# control.net
KiCad netlist of a schematic drawn in EAGLE
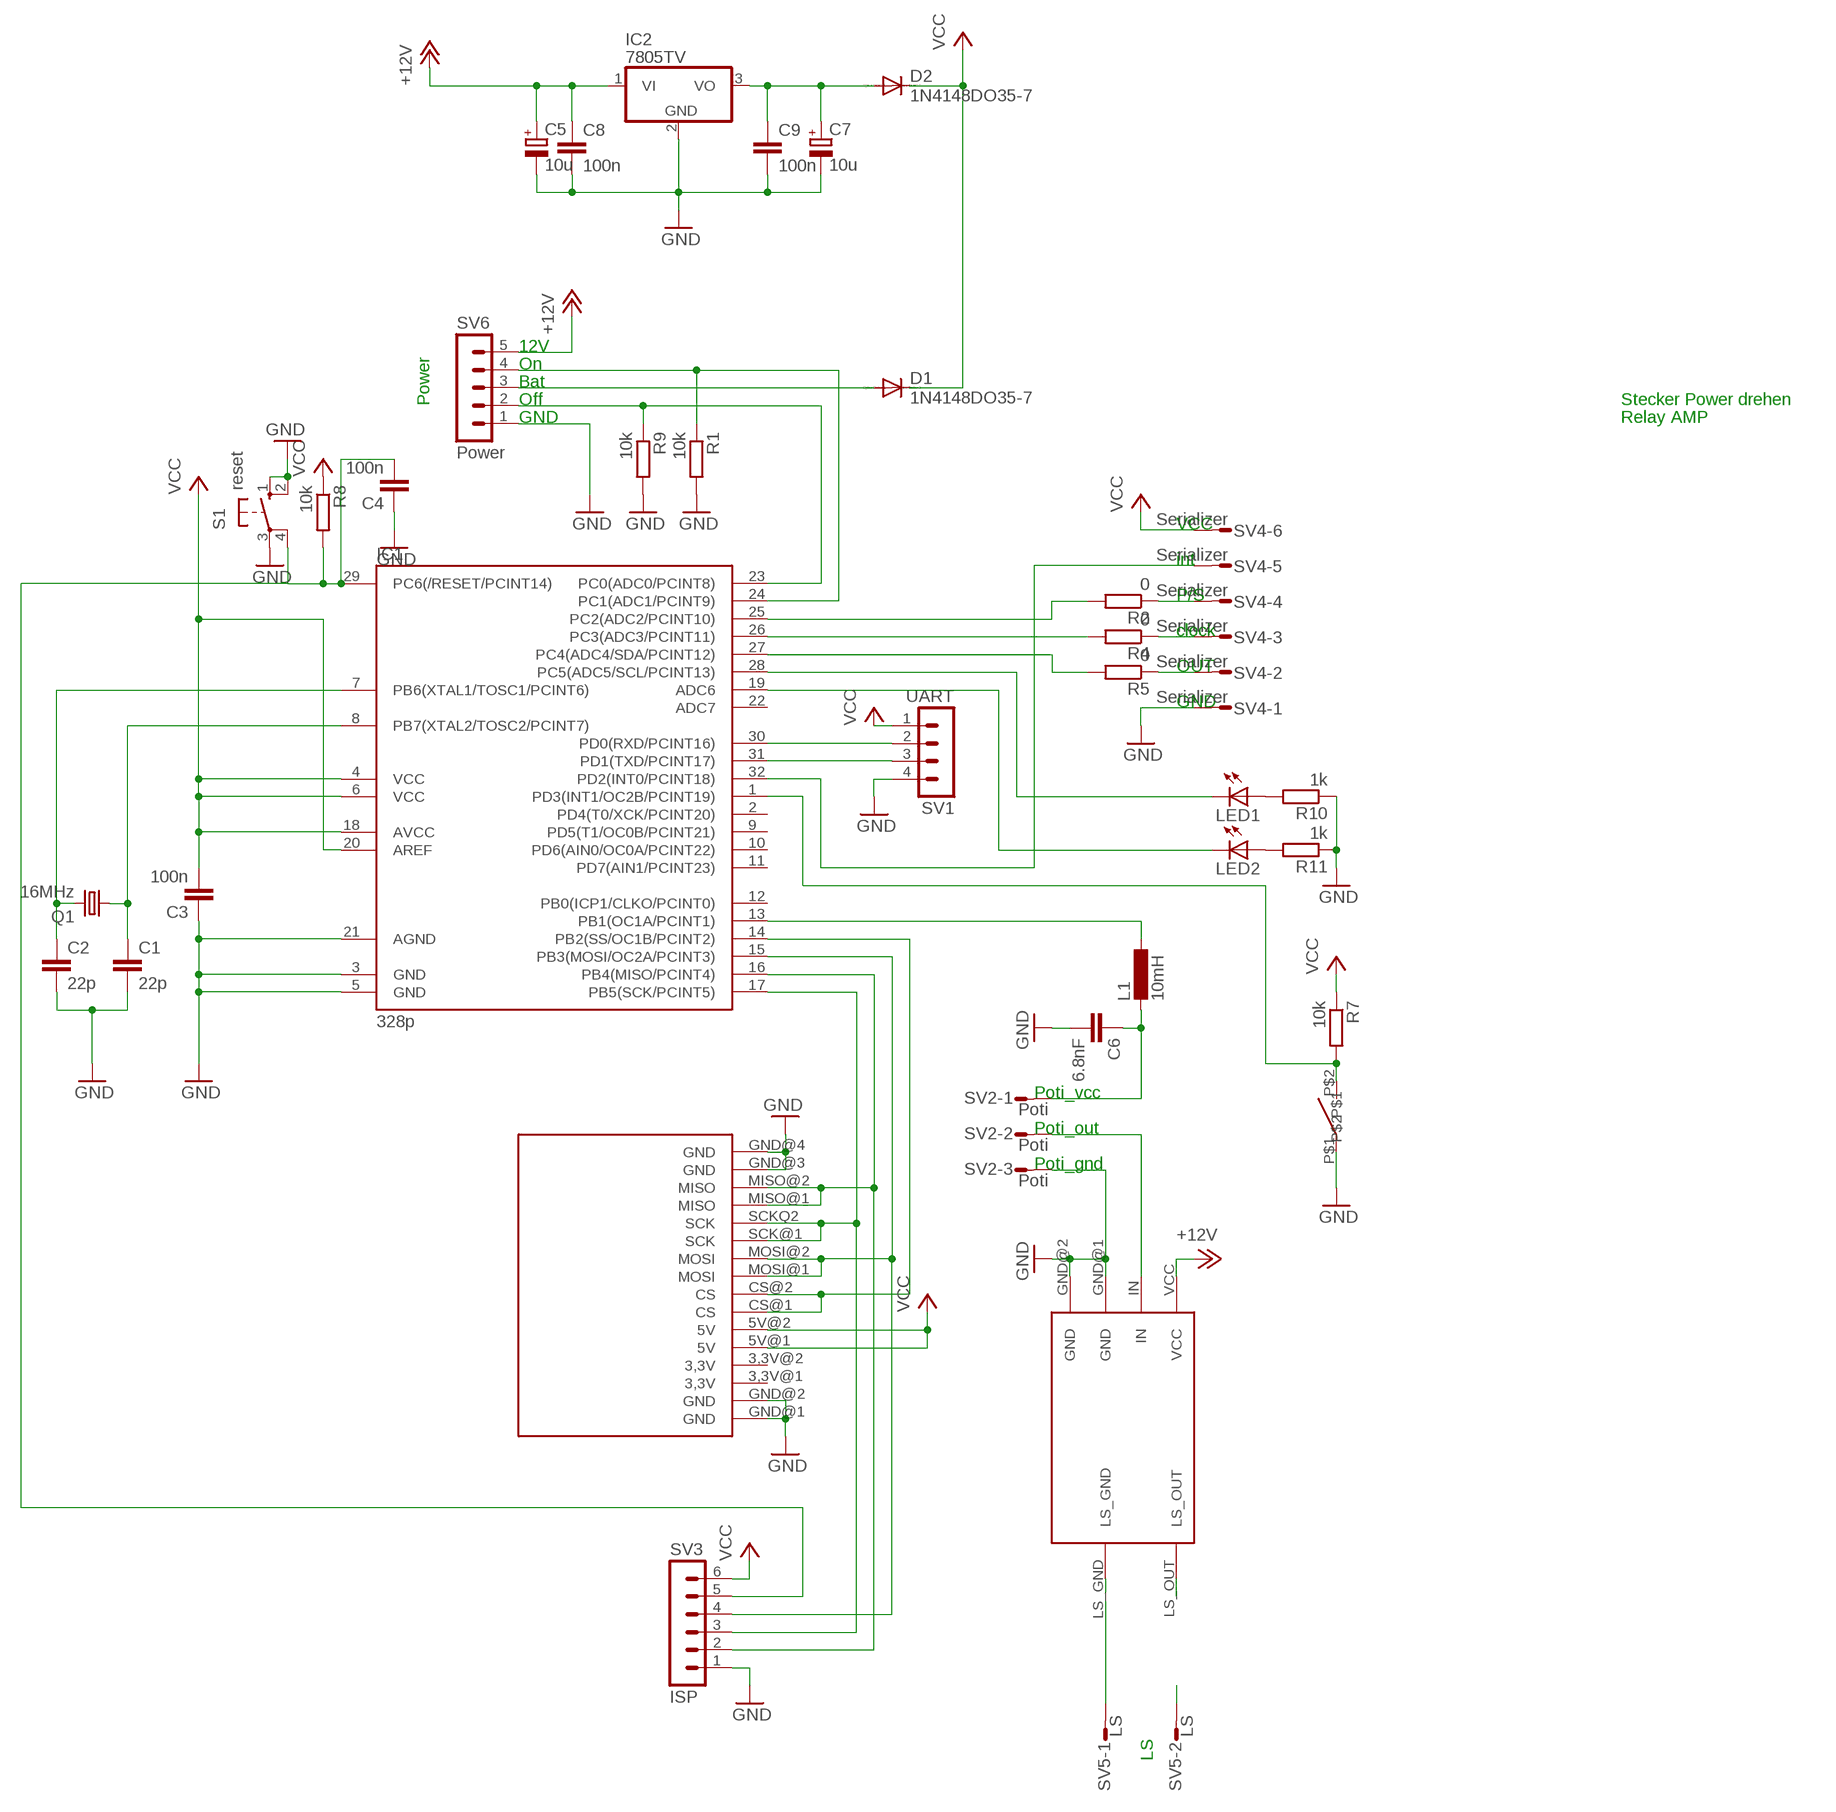
[diagram p0: schematic, sheet 1]

(export (version "E")
  (design (tool "Eeschema 10.0.6"))
  (components
    (comp (ref "C1")
      (value "22p")
      (footprint "eagle-import:C1206")
      (libsource (lib "eagle-import") (part "C-EUC1206"))
    )
    (comp (ref "C2")
      (value "22p")
      (footprint "eagle-import:C1206")
      (libsource (lib "eagle-import") (part "C-EUC1206"))
    )
    (comp (ref "C3")
      (value "100n")
      (footprint "eagle-import:C1206")
      (libsource (lib "eagle-import") (part "C-EUC1206"))
    )
    (comp (ref "C4")
      (value "100n")
      (footprint "eagle-import:C1206")
      (libsource (lib "eagle-import") (part "C-EUC1206"))
    )
    (comp (ref "C5")
      (value "10u")
      (footprint "eagle-import:E2,5-7")
      (libsource (lib "eagle-import") (part "CPOL-EUE2.5-7"))
    )
    (comp (ref "C6")
      (value "6.8nF")
      (footprint "eagle-import:C050-024X044")
      (libsource (lib "eagle-import") (part "C-EU050-024X044"))
    )
    (comp (ref "C7")
      (value "10u")
      (footprint "eagle-import:E2,5-7")
      (libsource (lib "eagle-import") (part "CPOL-EUE2.5-7"))
    )
    (comp (ref "C8")
      (value "100n")
      (footprint "eagle-import:C1206")
      (libsource (lib "eagle-import") (part "C-EUC1206"))
    )
    (comp (ref "C9")
      (value "100n")
      (footprint "eagle-import:C1206")
      (libsource (lib "eagle-import") (part "C-EUC1206"))
    )
    (comp (ref "D1")
      (value "1N4148DO35-7")
      (footprint "eagle-import:DO35-7")
      (libsource (lib "eagle-import") (part "1N4148DO35-7"))
    )
    (comp (ref "D2")
      (value "1N4148DO35-7")
      (footprint "eagle-import:DO35-7")
      (libsource (lib "eagle-import") (part "1N4148DO35-7"))
    )
    (comp (ref "IC1")
      (value "328p")
      (footprint "eagle-import:TQFP32-08")
      (libsource (lib "eagle-import") (part "MEGA48/88/168-AU"))
    )
    (comp (ref "IC2")
      (value "7805TV")
      (footprint "eagle-import:TO220V")
      (libsource (lib "eagle-import") (part "78TV05"))
    )
    (comp (ref "L1")
      (value "10mH")
      (footprint "eagle-import:0207_5V")
      (libsource (lib "eagle-import") (part "L-EU0207/5V"))
    )
    (comp (ref "LED1")
      (value "LEDCHIPLED_1206")
      (footprint "eagle-import:CHIPLED_1206")
      (libsource (lib "eagle-import") (part "LEDCHIPLED_1206"))
    )
    (comp (ref "LED2")
      (value "LEDCHIPLED_1206")
      (footprint "eagle-import:CHIPLED_1206")
      (libsource (lib "eagle-import") (part "LEDCHIPLED_1206"))
    )
    (comp (ref "Q1")
      (value "16MHz")
      (footprint "eagle-import:HC49UP")
      (libsource (lib "eagle-import") (part "CRYSTALHC49UP"))
    )
    (comp (ref "R1")
      (value "10k")
      (footprint "eagle-import:M1206")
      (libsource (lib "eagle-import") (part "R-EU_M1206"))
    )
    (comp (ref "R2")
      (value "0")
      (footprint "eagle-import:M1206")
      (libsource (lib "eagle-import") (part "R-EU_M1206"))
    )
    (comp (ref "R4")
      (value "0")
      (footprint "eagle-import:M1206")
      (libsource (lib "eagle-import") (part "R-EU_M1206"))
    )
    (comp (ref "R5")
      (value "0")
      (footprint "eagle-import:M1206")
      (libsource (lib "eagle-import") (part "R-EU_M1206"))
    )
    (comp (ref "R7")
      (value "10k")
      (footprint "eagle-import:M1206")
      (libsource (lib "eagle-import") (part "R-EU_M1206"))
    )
    (comp (ref "R8")
      (value "10k")
      (footprint "eagle-import:M1206")
      (libsource (lib "eagle-import") (part "R-EU_M1206"))
    )
    (comp (ref "R9")
      (value "10k")
      (footprint "eagle-import:M1206")
      (libsource (lib "eagle-import") (part "R-EU_M1206"))
    )
    (comp (ref "R10")
      (value "1k")
      (footprint "eagle-import:M1206")
      (libsource (lib "eagle-import") (part "R-EU_M1206"))
    )
    (comp (ref "R11")
      (value "1k")
      (footprint "eagle-import:M1206")
      (libsource (lib "eagle-import") (part "R-EU_M1206"))
    )
    (comp (ref "S1")
      (value "reset")
      (footprint "eagle-import:B3F-10XX")
      (fields (field (name "MPN") "B3F-1000"))
      (libsource (lib "eagle-import") (part "10-XX"))
    )
    (comp (ref "SV1")
      (value "UART")
      (footprint "eagle-import:MA04-1")
      (libsource (lib "eagle-import") (part "MA04-1"))
    )
    (comp (ref "SV2")
      (value "Poti")
      (footprint "eagle-import:S03P")
      (libsource (lib "eagle-import") (part "S03P"))
    )
    (comp (ref "SV3")
      (value "ISP")
      (footprint "eagle-import:MA06-1")
      (libsource (lib "eagle-import") (part "MA06-1"))
    )
    (comp (ref "SV4")
      (value "Serializer")
      (footprint "eagle-import:S06P")
      (libsource (lib "eagle-import") (part "S06P"))
    )
    (comp (ref "SV5")
      (value "LS")
      (footprint "eagle-import:S02P")
      (libsource (lib "eagle-import") (part "S02P"))
    )
    (comp (ref "SV6")
      (value "Power")
      (footprint "eagle-import:MA05-1")
      (libsource (lib "eagle-import") (part "MA05-1"))
    )
    (comp (ref "U$1")
      (value "TILT")
      (footprint "eagle-import:TILT")
      (libsource (lib "eagle-import") (part "TILT"))
    )
    (comp (ref "U$2")
      (value "AMP")
      (footprint "eagle-import:AMP")
      (libsource (lib "eagle-import") (part "AMP"))
    )
    (comp (ref "U$3")
      (value "SD_CARD_HOLDER")
      (footprint "eagle-import:SD_CARD_HOLDER")
      (libsource (lib "eagle-import") (part "SD_CARD_HOLDER"))
    )
  )
  (nets
    (net (code "1") (name "+12V") (class "Default")
      (node (ref "C5") (pin "+") (pinfunction "+_+") (pintype "passive"))
      (node (ref "C8") (pin "1") (pinfunction "1_1") (pintype "passive"))
      (node (ref "IC2") (pin "1") (pinfunction "VI_1") (pintype "input"))
      (node (ref "SV6") (pin "5") (pinfunction "5_5") (pintype "passive"))
      (node (ref "U$2") (pin "VCC") (pinfunction "VCC_VCC") (pintype "bidirectional"))
    )
    (net (code "2") (name "GND") (class "Default")
      (node (ref "C1") (pin "2") (pinfunction "2_2") (pintype "passive"))
      (node (ref "C2") (pin "2") (pinfunction "2_2") (pintype "passive"))
      (node (ref "C3") (pin "1") (pinfunction "1_1") (pintype "passive"))
      (node (ref "C4") (pin "1") (pinfunction "1_1") (pintype "passive"))
      (node (ref "C5") (pin "-") (pinfunction "-_-") (pintype "passive"))
      (node (ref "C6") (pin "2") (pinfunction "2_2") (pintype "passive"))
      (node (ref "C7") (pin "-") (pinfunction "-_-") (pintype "passive"))
      (node (ref "C8") (pin "2") (pinfunction "2_2") (pintype "passive"))
      (node (ref "C9") (pin "2") (pinfunction "2_2") (pintype "passive"))
      (node (ref "IC1") (pin "21") (pinfunction "AGND_21") (pintype "power_in"))
      (node (ref "IC1") (pin "3") (pinfunction "GND_3") (pintype "power_in"))
      (node (ref "IC1") (pin "5") (pinfunction "GND_5") (pintype "power_in"))
      (node (ref "IC2") (pin "2") (pinfunction "GND_2") (pintype "passive"))
      (node (ref "R1") (pin "2") (pinfunction "2_2") (pintype "passive"))
      (node (ref "R10") (pin "1") (pinfunction "1_1") (pintype "passive"))
      (node (ref "R11") (pin "1") (pinfunction "1_1") (pintype "passive"))
      (node (ref "R9") (pin "2") (pinfunction "2_2") (pintype "passive"))
      (node (ref "S1") (pin "1") (pinfunction "S_1") (pintype "passive"))
      (node (ref "S1") (pin "2") (pinfunction "S1_2") (pintype "passive"))
      (node (ref "S1") (pin "3") (pinfunction "P_3") (pintype "passive"))
      (node (ref "SV1") (pin "4") (pinfunction "4_4") (pintype "passive"))
      (node (ref "SV2") (pin "3") (pinfunction "S_3") (pintype "passive"))
      (node (ref "SV3") (pin "1") (pinfunction "1_1") (pintype "passive"))
      (node (ref "SV4") (pin "1") (pinfunction "S_1") (pintype "passive"))
      (node (ref "SV6") (pin "1") (pinfunction "1_1") (pintype "passive"))
      (node (ref "U$1") (pin "P$1") (pinfunction "P$1_P$1") (pintype "bidirectional"))
      (node (ref "U$2") (pin "GND@1") (pinfunction "GND_GND@1") (pintype "bidirectional"))
      (node (ref "U$2") (pin "GND@2") (pinfunction "GND_GND@2") (pintype "bidirectional"))
      (node (ref "U$3") (pin "GND@1") (pinfunction "GND_GND@1") (pintype "bidirectional"))
      (node (ref "U$3") (pin "GND@2") (pinfunction "GND_GND@2") (pintype "bidirectional"))
      (node (ref "U$3") (pin "GND@3") (pinfunction "GND_GND@3") (pintype "bidirectional"))
      (node (ref "U$3") (pin "GND@4") (pinfunction "GND_GND@4") (pintype "bidirectional"))
    )
    (net (code "3") (name "Net-(D1-PadA)") (class "Default")
      (node (ref "D1") (pin "A") (pinfunction "A_A") (pintype "passive"))
      (node (ref "SV6") (pin "3") (pinfunction "3_3") (pintype "passive"))
    )
    (net (code "4") (name "Net-(IC1-ADC6)") (class "Default")
      (node (ref "IC1") (pin "19") (pinfunction "ADC6_19") (pintype "passive"))
      (node (ref "LED2") (pin "C") (pinfunction "C_C") (pintype "passive"))
    )
    (net (code "5") (name "Net-(IC1-PB1(OC1A{slash}PCINT1))") (class "Default")
      (node (ref "IC1") (pin "13") (pinfunction "PB1(OC1A/PCINT1)_13") (pintype "bidirectional"))
      (node (ref "L1") (pin "1") (pinfunction "1_1") (pintype "passive"))
    )
    (net (code "6") (name "Net-(IC1-PB2(SS{slash}OC1B{slash}PCINT2))") (class "Default")
      (node (ref "IC1") (pin "14") (pinfunction "PB2(SS/OC1B/PCINT2)_14") (pintype "bidirectional"))
      (node (ref "U$3") (pin "CS@1") (pinfunction "CS_CS@1") (pintype "bidirectional"))
      (node (ref "U$3") (pin "CS@2") (pinfunction "CS_CS@2") (pintype "bidirectional"))
    )
    (net (code "7") (name "Net-(IC1-PB3(MOSI{slash}OC2A{slash}PCINT3))") (class "Default")
      (node (ref "IC1") (pin "15") (pinfunction "PB3(MOSI/OC2A/PCINT3)_15") (pintype "bidirectional"))
      (node (ref "SV3") (pin "4") (pinfunction "4_4") (pintype "passive"))
      (node (ref "U$3") (pin "MOSI@1") (pinfunction "MOSI_MOSI@1") (pintype "bidirectional"))
      (node (ref "U$3") (pin "MOSI@2") (pinfunction "MOSI_MOSI@2") (pintype "bidirectional"))
    )
    (net (code "8") (name "Net-(IC1-PB4(MISO{slash}PCINT4))") (class "Default")
      (node (ref "IC1") (pin "16") (pinfunction "PB4(MISO/PCINT4)_16") (pintype "bidirectional"))
      (node (ref "SV3") (pin "2") (pinfunction "2_2") (pintype "passive"))
      (node (ref "U$3") (pin "MISO@1") (pinfunction "MISO_MISO@1") (pintype "bidirectional"))
      (node (ref "U$3") (pin "MISO@2") (pinfunction "MISO_MISO@2") (pintype "bidirectional"))
    )
    (net (code "9") (name "Net-(IC1-PB5(SCK{slash}PCINT5))") (class "Default")
      (node (ref "IC1") (pin "17") (pinfunction "PB5(SCK/PCINT5)_17") (pintype "bidirectional"))
      (node (ref "SV3") (pin "3") (pinfunction "3_3") (pintype "passive"))
      (node (ref "U$3") (pin "SCK@1") (pinfunction "SCK_SCK@1") (pintype "bidirectional"))
      (node (ref "U$3") (pin "SCKQ2") (pinfunction "SCK_SCKQ2") (pintype "bidirectional"))
    )
    (net (code "10") (name "Net-(IC1-PB6(XTAL1{slash}TOSC1{slash}PCINT6))") (class "Default")
      (node (ref "C2") (pin "1") (pinfunction "1_1") (pintype "passive"))
      (node (ref "IC1") (pin "7") (pinfunction "PB6(XTAL1/TOSC1/PCINT6)_7") (pintype "bidirectional"))
      (node (ref "Q1") (pin "2") (pinfunction "2_2") (pintype "passive"))
    )
    (net (code "11") (name "Net-(IC1-PB7(XTAL2{slash}TOSC2{slash}PCINT7))") (class "Default")
      (node (ref "C1") (pin "1") (pinfunction "1_1") (pintype "passive"))
      (node (ref "IC1") (pin "8") (pinfunction "PB7(XTAL2/TOSC2/PCINT7)_8") (pintype "bidirectional"))
      (node (ref "Q1") (pin "1") (pinfunction "1_1") (pintype "passive"))
    )
    (net (code "12") (name "Net-(IC1-PC0(ADC0{slash}PCINT8))") (class "Default")
      (node (ref "IC1") (pin "23") (pinfunction "PC0(ADC0/PCINT8)_23") (pintype "bidirectional"))
      (node (ref "R9") (pin "1") (pinfunction "1_1") (pintype "passive"))
      (node (ref "SV6") (pin "2") (pinfunction "2_2") (pintype "passive"))
    )
    (net (code "13") (name "Net-(IC1-PC1(ADC1{slash}PCINT9))") (class "Default")
      (node (ref "IC1") (pin "24") (pinfunction "PC1(ADC1/PCINT9)_24") (pintype "bidirectional"))
      (node (ref "R1") (pin "1") (pinfunction "1_1") (pintype "passive"))
      (node (ref "SV6") (pin "4") (pinfunction "4_4") (pintype "passive"))
    )
    (net (code "14") (name "Net-(IC1-PC2(ADC2{slash}PCINT10))") (class "Default")
      (node (ref "IC1") (pin "25") (pinfunction "PC2(ADC2/PCINT10)_25") (pintype "bidirectional"))
      (node (ref "R2") (pin "2") (pinfunction "2_2") (pintype "passive"))
    )
    (net (code "15") (name "Net-(IC1-PC3(ADC3{slash}PCINT11))") (class "Default")
      (node (ref "IC1") (pin "26") (pinfunction "PC3(ADC3/PCINT11)_26") (pintype "bidirectional"))
      (node (ref "R4") (pin "2") (pinfunction "2_2") (pintype "passive"))
    )
    (net (code "16") (name "Net-(IC1-PC4(ADC4{slash}SDA{slash}PCINT12))") (class "Default")
      (node (ref "IC1") (pin "27") (pinfunction "PC4(ADC4/SDA/PCINT12)_27") (pintype "bidirectional"))
      (node (ref "R5") (pin "2") (pinfunction "2_2") (pintype "passive"))
    )
    (net (code "17") (name "Net-(IC1-PC5(ADC5{slash}SCL{slash}PCINT13))") (class "Default")
      (node (ref "IC1") (pin "28") (pinfunction "PC5(ADC5/SCL/PCINT13)_28") (pintype "bidirectional"))
      (node (ref "LED1") (pin "C") (pinfunction "C_C") (pintype "passive"))
    )
    (net (code "18") (name "Net-(IC1-PC6({slash}RESET{slash}PCINT14))") (class "Default")
      (node (ref "C4") (pin "2") (pinfunction "2_2") (pintype "passive"))
      (node (ref "IC1") (pin "29") (pinfunction "PC6(/RESET/PCINT14)_29") (pintype "bidirectional"))
      (node (ref "R8") (pin "2") (pinfunction "2_2") (pintype "passive"))
      (node (ref "S1") (pin "4") (pinfunction "P1_4") (pintype "passive"))
      (node (ref "SV3") (pin "5") (pinfunction "5_5") (pintype "passive"))
    )
    (net (code "19") (name "Net-(IC1-PD0(RXD{slash}PCINT16))") (class "Default")
      (node (ref "IC1") (pin "30") (pinfunction "PD0(RXD/PCINT16)_30") (pintype "bidirectional"))
      (node (ref "SV1") (pin "2") (pinfunction "2_2") (pintype "passive"))
    )
    (net (code "20") (name "Net-(IC1-PD1(TXD{slash}PCINT17))") (class "Default")
      (node (ref "IC1") (pin "31") (pinfunction "PD1(TXD/PCINT17)_31") (pintype "bidirectional"))
      (node (ref "SV1") (pin "3") (pinfunction "3_3") (pintype "passive"))
    )
    (net (code "21") (name "Net-(IC1-PD2(INT0{slash}PCINT18))") (class "Default")
      (node (ref "IC1") (pin "32") (pinfunction "PD2(INT0/PCINT18)_32") (pintype "bidirectional"))
      (node (ref "SV4") (pin "5") (pinfunction "S_5") (pintype "passive"))
    )
    (net (code "22") (name "Net-(IC1-PD3(INT1{slash}OC2B{slash}PCINT19))") (class "Default")
      (node (ref "IC1") (pin "1") (pinfunction "PD3(INT1/OC2B/PCINT19)_1") (pintype "bidirectional"))
      (node (ref "R7") (pin "2") (pinfunction "2_2") (pintype "passive"))
      (node (ref "U$1") (pin "P$2") (pinfunction "P$2_P$2") (pintype "bidirectional"))
    )
    (net (code "23") (name "Net-(IC2-VO)") (class "Default")
      (node (ref "C7") (pin "+") (pinfunction "+_+") (pintype "passive"))
      (node (ref "C9") (pin "1") (pinfunction "1_1") (pintype "passive"))
      (node (ref "D2") (pin "A") (pinfunction "A_A") (pintype "passive"))
      (node (ref "IC2") (pin "3") (pinfunction "VO_3") (pintype "passive"))
    )
    (net (code "24") (name "Net-(LED1-PadA)") (class "Default")
      (node (ref "LED1") (pin "A") (pinfunction "A_A") (pintype "passive"))
      (node (ref "R10") (pin "2") (pinfunction "2_2") (pintype "passive"))
    )
    (net (code "25") (name "Net-(LED2-PadA)") (class "Default")
      (node (ref "LED2") (pin "A") (pinfunction "A_A") (pintype "passive"))
      (node (ref "R11") (pin "2") (pinfunction "2_2") (pintype "passive"))
    )
    (net (code "26") (name "Net-(SV2A-S)") (class "Default")
      (node (ref "C6") (pin "1") (pinfunction "1_1") (pintype "passive"))
      (node (ref "L1") (pin "2") (pinfunction "2_2") (pintype "passive"))
      (node (ref "SV2") (pin "1") (pinfunction "S_1") (pintype "passive"))
    )
    (net (code "27") (name "Net-(SV2B-S)") (class "Default")
      (node (ref "SV2") (pin "2") (pinfunction "S_2") (pintype "passive"))
      (node (ref "U$2") (pin "IN") (pinfunction "IN_IN") (pintype "bidirectional"))
    )
    (net (code "28") (name "Net-(SV4B-S)") (class "Default")
      (node (ref "R5") (pin "1") (pinfunction "1_1") (pintype "passive"))
      (node (ref "SV4") (pin "2") (pinfunction "S_2") (pintype "passive"))
    )
    (net (code "29") (name "Net-(SV4C-S)") (class "Default")
      (node (ref "R4") (pin "1") (pinfunction "1_1") (pintype "passive"))
      (node (ref "SV4") (pin "3") (pinfunction "S_3") (pintype "passive"))
    )
    (net (code "30") (name "Net-(SV4D-S)") (class "Default")
      (node (ref "R2") (pin "1") (pinfunction "1_1") (pintype "passive"))
      (node (ref "SV4") (pin "4") (pinfunction "S_4") (pintype "passive"))
    )
    (net (code "31") (name "Net-(SV5A-S)") (class "Default")
      (node (ref "SV5") (pin "1") (pinfunction "S_1") (pintype "passive"))
      (node (ref "U$2") (pin "LS_GND") (pinfunction "LS_GND_LS_GND") (pintype "bidirectional"))
    )
    (net (code "32") (name "VCC") (class "Default")
      (node (ref "C3") (pin "2") (pinfunction "2_2") (pintype "passive"))
      (node (ref "D1") (pin "C") (pinfunction "C_C") (pintype "passive"))
      (node (ref "D2") (pin "C") (pinfunction "C_C") (pintype "passive"))
      (node (ref "IC1") (pin "18") (pinfunction "AVCC_18") (pintype "passive"))
      (node (ref "IC1") (pin "20") (pinfunction "AREF_20") (pintype "passive"))
      (node (ref "IC1") (pin "4") (pinfunction "VCC_4") (pintype "power_in"))
      (node (ref "IC1") (pin "6") (pinfunction "VCC_6") (pintype "power_in"))
      (node (ref "R7") (pin "1") (pinfunction "1_1") (pintype "passive"))
      (node (ref "R8") (pin "1") (pinfunction "1_1") (pintype "passive"))
      (node (ref "SV1") (pin "1") (pinfunction "1_1") (pintype "passive"))
      (node (ref "SV3") (pin "6") (pinfunction "6_6") (pintype "passive"))
      (node (ref "SV4") (pin "6") (pinfunction "S_6") (pintype "passive"))
      (node (ref "U$3") (pin "5V@1") (pinfunction "5V_5V@1") (pintype "bidirectional"))
      (node (ref "U$3") (pin "5V@2") (pinfunction "5V_5V@2") (pintype "bidirectional"))
    )
    (net (code "33") (name "unconnected-(IC1-ADC7-Pad22)") (class "Default")
      (node (ref "IC1") (pin "22") (pinfunction "ADC7_22") (pintype "passive"))
    )
    (net (code "34") (name "unconnected-(IC1-PB0(ICP1{slash}CLKO{slash}PCINT0)-Pad12)") (class "Default")
      (node (ref "IC1") (pin "12") (pinfunction "PB0(ICP1/CLKO/PCINT0)_12") (pintype "bidirectional"))
    )
    (net (code "35") (name "unconnected-(IC1-PD4(T0{slash}XCK{slash}PCINT20)-Pad2)") (class "Default")
      (node (ref "IC1") (pin "2") (pinfunction "PD4(T0/XCK/PCINT20)_2") (pintype "bidirectional"))
    )
    (net (code "36") (name "unconnected-(IC1-PD5(T1{slash}OC0B{slash}PCINT21)-Pad9)") (class "Default")
      (node (ref "IC1") (pin "9") (pinfunction "PD5(T1/OC0B/PCINT21)_9") (pintype "bidirectional"))
    )
    (net (code "37") (name "unconnected-(IC1-PD6(AIN0{slash}OC0A{slash}PCINT22)-Pad10)") (class "Default")
      (node (ref "IC1") (pin "10") (pinfunction "PD6(AIN0/OC0A/PCINT22)_10") (pintype "bidirectional"))
    )
    (net (code "38") (name "unconnected-(IC1-PD7(AIN1{slash}PCINT23)-Pad11)") (class "Default")
      (node (ref "IC1") (pin "11") (pinfunction "PD7(AIN1/PCINT23)_11") (pintype "bidirectional"))
    )
    (net (code "39") (name "unconnected-(SV5B-S-Pad2)") (class "Default")
      (node (ref "SV5") (pin "2") (pinfunction "S_2") (pintype "passive"))
    )
    (net (code "40") (name "unconnected-(U$2-PadLS_OUT)") (class "Default")
      (node (ref "U$2") (pin "LS_OUT") (pinfunction "LS_OUT_LS_OUT") (pintype "bidirectional"))
    )
    (net (code "41") (name "unconnected-(U$3-3,3V-Pad3,3V@1)") (class "Default")
      (node (ref "U$3") (pin "3,3V@1") (pinfunction "3,3V_3,3V@1") (pintype "bidirectional"))
    )
    (net (code "42") (name "unconnected-(U$3-3,3V-Pad3,3V@2)") (class "Default")
      (node (ref "U$3") (pin "3,3V@2") (pinfunction "3,3V_3,3V@2") (pintype "bidirectional"))
    )
  )
)
